# WIFIModule.net
KiCad netlist of a schematic drawn in Altium Designer
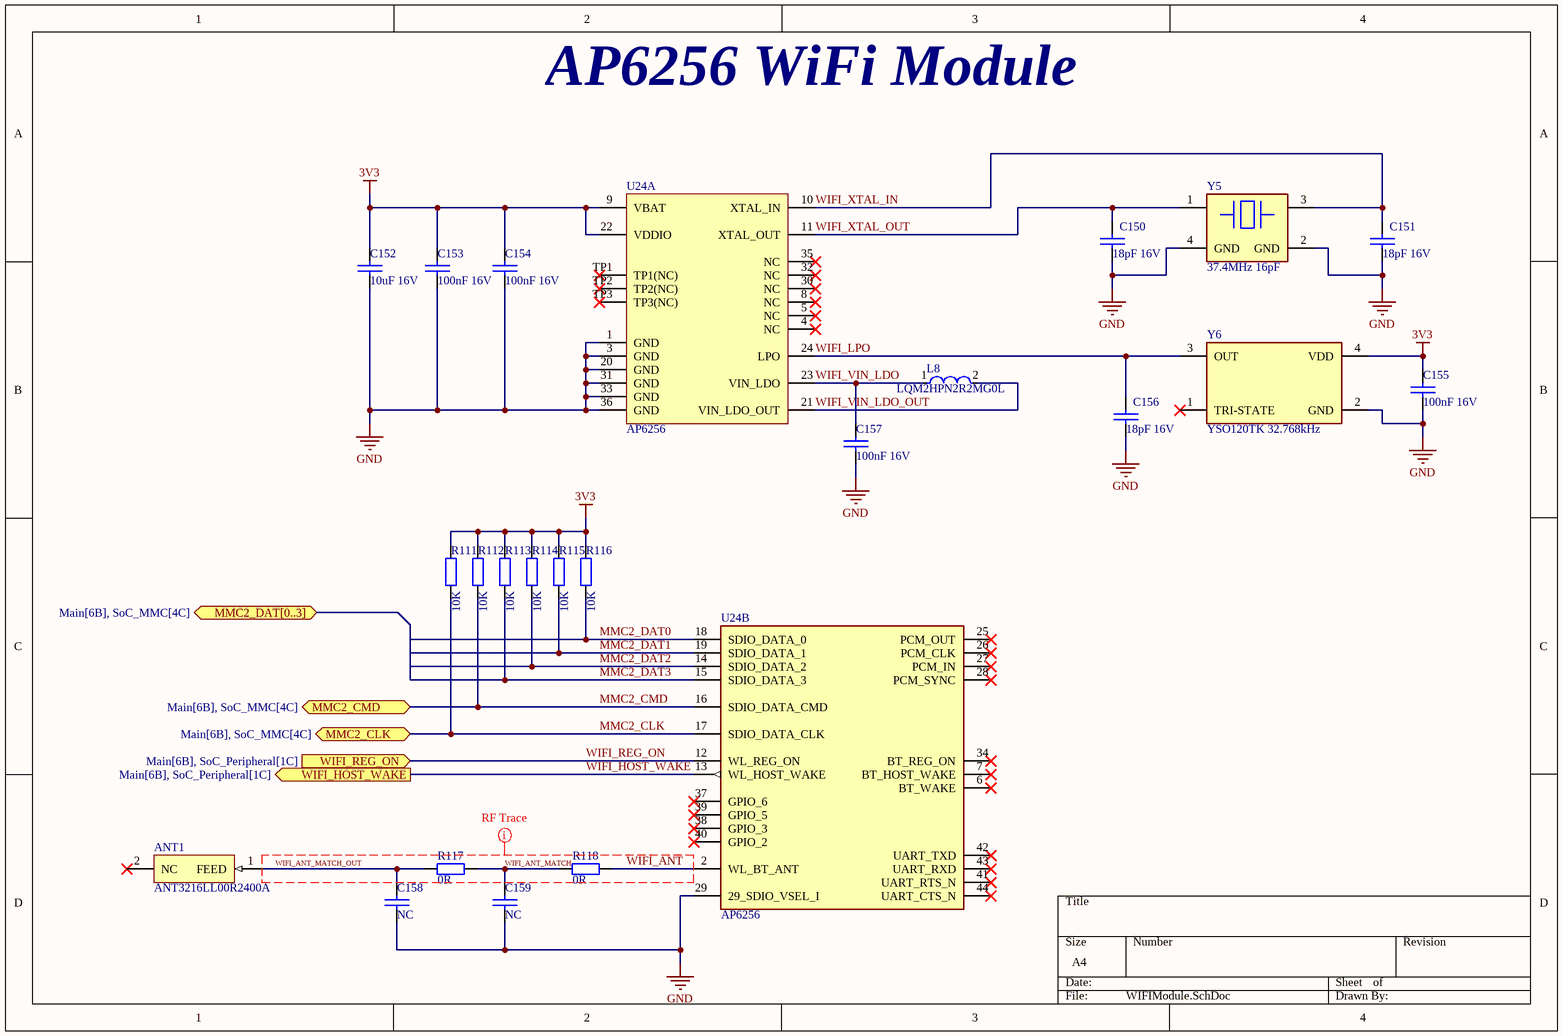
[diagram p0: WIFIModule.SchDoc]

(export (version "E")
  (design (tool "Eeschema 10.0.6"))
  (components
    (comp (ref "ANT1")
      (value "ANT3216LL00R2400A")
      (footprint "ANT_1206")
      (description "5.05dBi Chip Antenna Linear 160MHz 2450MHz 1W 1206 Antennas ROHS")
      (fields (field (name "MANUFACTURER") "YAGEO"))
      (libsource (lib "tor1kkLib") (part "ANT3216LL00R2400A"))
    )
    (comp (ref "C150")
      (value "18pF 16V")
      (footprint "C_0402")
      (description "Capacitor 0402 SMD")
      (libsource (lib "tor1kkLib") (part "C_0402"))
    )
    (comp (ref "C151")
      (value "18pF 16V")
      (footprint "C_0402")
      (description "Capacitor 0402 SMD")
      (libsource (lib "tor1kkLib") (part "C_0402"))
    )
    (comp (ref "C152")
      (value "10uF 16V")
      (footprint "C_0603")
      (description "Capacitor 0603 SMD")
      (libsource (lib "tor1kkLib") (part "C_0603"))
    )
    (comp (ref "C153")
      (value "100nF 16V")
      (footprint "C_0402")
      (description "Capacitor 0402 SMD")
      (libsource (lib "tor1kkLib") (part "C_0402"))
    )
    (comp (ref "C154")
      (value "100nF 16V")
      (footprint "C_0402")
      (description "Capacitor 0402 SMD")
      (libsource (lib "tor1kkLib") (part "C_0402"))
    )
    (comp (ref "C155")
      (value "100nF 16V")
      (footprint "C_0402")
      (description "Capacitor 0402 SMD")
      (libsource (lib "tor1kkLib") (part "C_0402"))
    )
    (comp (ref "C156")
      (value "18pF 16V")
      (footprint "C_0402")
      (description "Capacitor 0402 SMD")
      (libsource (lib "tor1kkLib") (part "C_0402"))
    )
    (comp (ref "C157")
      (value "100nF 16V")
      (footprint "C_0402")
      (description "Capacitor 0402 SMD")
      (libsource (lib "tor1kkLib") (part "C_0402"))
    )
    (comp (ref "C158")
      (value "NC")
      (footprint "C_0402")
      (description "Capacitor 0402 SMD")
      (libsource (lib "tor1kkLib") (part "C_0402"))
    )
    (comp (ref "C159")
      (value "NC")
      (footprint "C_0402")
      (description "Capacitor 0402 SMD")
      (libsource (lib "tor1kkLib") (part "C_0402"))
    )
    (comp (ref "L8")
      (value "LQM2HPN2R2MG0L")
      (footprint "FP-LQM2HPN_G0-IPC_C")
      (description "Multilayer Type Inductor for Power Lines, 1008 (2520), 2.2μH, 20%, 0.1Ω, 1.3A")
      (fields (field (name "TOLERANCE") "20%"))
      (libsource (lib "Altium Content Vault") (part "725321dda6339637d4d059423bc1c3c"))
    )
    (comp (ref "R111")
      (value "10K")
      (footprint "R_0402")
      (description "Resistor 0402 SMD")
      (libsource (lib "tor1kkLib") (part "R_0402"))
    )
    (comp (ref "R112")
      (value "10K")
      (footprint "R_0402")
      (description "Resistor 0402 SMD")
      (libsource (lib "tor1kkLib") (part "R_0402"))
    )
    (comp (ref "R113")
      (value "10K")
      (footprint "R_0402")
      (description "Resistor 0402 SMD")
      (libsource (lib "tor1kkLib") (part "R_0402"))
    )
    (comp (ref "R114")
      (value "10K")
      (footprint "R_0402")
      (description "Resistor 0402 SMD")
      (libsource (lib "tor1kkLib") (part "R_0402"))
    )
    (comp (ref "R115")
      (value "10K")
      (footprint "R_0402")
      (description "Resistor 0402 SMD")
      (libsource (lib "tor1kkLib") (part "R_0402"))
    )
    (comp (ref "R116")
      (value "10K")
      (footprint "R_0402")
      (description "Resistor 0402 SMD")
      (libsource (lib "tor1kkLib") (part "R_0402"))
    )
    (comp (ref "R117")
      (value "0R")
      (footprint "R_0402")
      (description "Resistor 0402 SMD")
      (libsource (lib "") (part "R_0402_1"))
    )
    (comp (ref "R118")
      (value "0R")
      (footprint "R_0402")
      (description "Resistor 0402 SMD")
      (libsource (lib "") (part "R_0402_1"))
    )
    (comp (ref "U24")
      (value "AP6256")
      (footprint "AP6256")
      (description "Wi-Fi and Bluetooth 802.11a/b/g/n/ac")
      (fields (field (name "MANUFACTURER") "AMPAK Tech"))
      (libsource (lib "tor1kkLib") (part "AP6256"))
    )
    (comp (ref "Y5")
      (value "37.4MHz 16pF")
      (footprint "CRYSTAL_SMD3225-4P")
      (description "37.4MHz 16pF ±10ppm ±10ppm SMD3225-4P Crystals ROHS")
      (fields
        (field (name "MANUFACTURER") "Hosonic Elec")
        (field (name "MANUFACTURER PART NUMBER") "E3SB37E0X0004E")
      )
      (libsource (lib "tor1kkLib") (part "E3SB37E0X0004E"))
    )
    (comp (ref "Y6")
      (value "YSO120TK 32.768kHz")
      (footprint "CRYSTAL_SMD3225-4P")
      (description "1.8V~3.3V ±10ppm ±20ppm CMOS 32.768kHz SMD3225-4P Crystal Oscillators ROHS")
      (fields
        (field (name "MANUFACTURER") "YXC Crystal Oscillators")
        (field (name "MANUFACTURER PART NUMBER") "OK2EL89CJI-111YLC-32.768K")
      )
      (libsource (lib "tor1kkLib") (part "YSO120TK"))
    )
  )
  (nets
    (net (code "1") (name "/MMC2_CLK") (class "Default")
      (node (ref "R111") (pin "1") (pintype "passive"))
      (node (ref "U24") (pin "17") (pinfunction "SDIO_DATA_CLK_17") (pintype "passive"))
    )
    (net (code "2") (name "/MMC2_CMD") (class "Default")
      (node (ref "R112") (pin "1") (pintype "passive"))
      (node (ref "U24") (pin "16") (pinfunction "SDIO_DATA_CMD_16") (pintype "passive"))
    )
    (net (code "3") (name "/MMC2_DAT0") (class "Default")
      (node (ref "R116") (pin "1") (pintype "passive"))
      (node (ref "U24") (pin "18") (pinfunction "SDIO_DATA_0_18") (pintype "passive"))
    )
    (net (code "4") (name "/MMC2_DAT1") (class "Default")
      (node (ref "R115") (pin "1") (pintype "passive"))
      (node (ref "U24") (pin "19") (pinfunction "SDIO_DATA_1_19") (pintype "passive"))
    )
    (net (code "5") (name "/MMC2_DAT2") (class "Default")
      (node (ref "R114") (pin "1") (pintype "passive"))
      (node (ref "U24") (pin "14") (pinfunction "SDIO_DATA_2_14") (pintype "passive"))
    )
    (net (code "6") (name "/MMC2_DAT3") (class "Default")
      (node (ref "R113") (pin "1") (pintype "passive"))
      (node (ref "U24") (pin "15") (pinfunction "SDIO_DATA_3_15") (pintype "passive"))
    )
    (net (code "8") (name "/WIFI_ANT") (class "Default")
      (node (ref "R118") (pin "2") (pintype "passive"))
      (node (ref "U24") (pin "2") (pinfunction "WL_BT_ANT_2") (pintype "passive"))
    )
    (net (code "9") (name "/WIFI_ANT_MATCH") (class "Default")
      (node (ref "C159") (pin "1") (pintype "passive"))
      (node (ref "R117") (pin "2") (pintype "passive"))
      (node (ref "R118") (pin "1") (pintype "passive"))
    )
    (net (code "10") (name "/WIFI_ANT_MATCH_OUT") (class "Default")
      (node (ref "ANT1") (pin "1") (pinfunction "FEED_1") (pintype "input"))
      (node (ref "C158") (pin "1") (pintype "passive"))
      (node (ref "R117") (pin "1") (pintype "passive"))
    )
    (net (code "11") (name "/WIFI_HOST_WAKE") (class "Default")
      (node (ref "U24") (pin "13") (pinfunction "WL_HOST_WAKE_13") (pintype "output"))
    )
    (net (code "12") (name "/WIFI_LPO") (class "Default")
      (node (ref "C156") (pin "2") (pintype "passive"))
      (node (ref "U24") (pin "24") (pinfunction "LPO_24") (pintype "passive"))
      (node (ref "Y6") (pin "3") (pinfunction "OUT_3") (pintype "passive"))
    )
    (net (code "13") (name "/WIFI_REG_ON") (class "Default")
      (node (ref "U24") (pin "12") (pinfunction "WL_REG_ON_12") (pintype "passive"))
    )
    (net (code "14") (name "/WIFI_VIN_LDO") (class "Default")
      (node (ref "C157") (pin "1") (pintype "passive"))
      (node (ref "L8") (pin "1") (pinfunction "1_1") (pintype "passive"))
      (node (ref "U24") (pin "23") (pinfunction "VIN_LDO_23") (pintype "passive"))
    )
    (net (code "15") (name "/WIFI_VIN_LDO_OUT") (class "Default")
      (node (ref "L8") (pin "2") (pinfunction "2_2") (pintype "passive"))
      (node (ref "U24") (pin "21") (pinfunction "VIN_LDO_OUT_21") (pintype "passive"))
    )
    (net (code "16") (name "/WIFI_XTAL_IN") (class "Default")
      (node (ref "C151") (pin "2") (pintype "passive"))
      (node (ref "U24") (pin "10") (pinfunction "XTAL_IN_10") (pintype "passive"))
      (node (ref "Y5") (pin "3") (pinfunction "CRYSTAL_2_3") (pintype "passive"))
    )
    (net (code "17") (name "/WIFI_XTAL_OUT") (class "Default")
      (node (ref "C150") (pin "2") (pintype "passive"))
      (node (ref "U24") (pin "11") (pinfunction "XTAL_OUT_11") (pintype "passive"))
      (node (ref "Y5") (pin "1") (pinfunction "CRYSTAL_1_1") (pintype "passive"))
    )
    (net (code "18") (name "3V3") (class "Default")
      (node (ref "C152") (pin "1") (pintype "passive"))
      (node (ref "C153") (pin "1") (pintype "passive"))
      (node (ref "C154") (pin "1") (pintype "passive"))
      (node (ref "C155") (pin "1") (pintype "passive"))
      (node (ref "R111") (pin "2") (pintype "passive"))
      (node (ref "R112") (pin "2") (pintype "passive"))
      (node (ref "R113") (pin "2") (pintype "passive"))
      (node (ref "R114") (pin "2") (pintype "passive"))
      (node (ref "R115") (pin "2") (pintype "passive"))
      (node (ref "R116") (pin "2") (pintype "passive"))
      (node (ref "U24") (pin "22") (pinfunction "VDDIO_22") (pintype "passive"))
      (node (ref "U24") (pin "9") (pinfunction "VBAT_9") (pintype "passive"))
      (node (ref "Y6") (pin "4") (pinfunction "VDD_4") (pintype "passive"))
    )
    (net (code "19") (name "GND") (class "Default")
      (node (ref "C150") (pin "1") (pintype "passive"))
      (node (ref "C151") (pin "1") (pintype "passive"))
      (node (ref "C152") (pin "2") (pintype "passive"))
      (node (ref "C153") (pin "2") (pintype "passive"))
      (node (ref "C154") (pin "2") (pintype "passive"))
      (node (ref "C155") (pin "2") (pintype "passive"))
      (node (ref "C156") (pin "1") (pintype "passive"))
      (node (ref "C157") (pin "2") (pintype "passive"))
      (node (ref "C158") (pin "2") (pintype "passive"))
      (node (ref "C159") (pin "2") (pintype "passive"))
      (node (ref "U24") (pin "1") (pinfunction "GND_1") (pintype "passive"))
      (node (ref "U24") (pin "20") (pinfunction "GND_20") (pintype "passive"))
      (node (ref "U24") (pin "29") (pinfunction "29_SDIO_VSEL_I_29") (pintype "passive"))
      (node (ref "U24") (pin "3") (pinfunction "GND_3") (pintype "passive"))
      (node (ref "U24") (pin "31") (pinfunction "GND_31") (pintype "passive"))
      (node (ref "U24") (pin "33") (pinfunction "GND_33") (pintype "passive"))
      (node (ref "U24") (pin "36") (pinfunction "GND_36") (pintype "passive"))
      (node (ref "Y5") (pin "2") (pinfunction "GND_2") (pintype "passive"))
      (node (ref "Y5") (pin "4") (pinfunction "GND_4") (pintype "passive"))
      (node (ref "Y6") (pin "2") (pinfunction "GND_2") (pintype "passive"))
    )
    (net (code "20") (name "unconnected-(ANT1-NC-Pad2)") (class "Default")
      (node (ref "ANT1") (pin "2") (pinfunction "NC_2") (pintype "passive+no_connect"))
    )
    (net (code "21") (name "unconnected-(U24A-NC-Pad4)") (class "Default")
      (node (ref "U24") (pin "4") (pinfunction "NC_4") (pintype "passive+no_connect"))
    )
    (net (code "22") (name "unconnected-(U24A-NC-Pad5)") (class "Default")
      (node (ref "U24") (pin "5") (pinfunction "NC_5") (pintype "passive+no_connect"))
    )
    (net (code "23") (name "unconnected-(U24A-NC-Pad8)") (class "Default")
      (node (ref "U24") (pin "8") (pinfunction "NC_8") (pintype "passive+no_connect"))
    )
    (net (code "24") (name "unconnected-(U24A-NC-Pad30)") (class "Default")
      (node (ref "U24") (pin "30") (pinfunction "NC_30") (pintype "passive+no_connect"))
    )
    (net (code "25") (name "unconnected-(U24A-NC-Pad32)") (class "Default")
      (node (ref "U24") (pin "32") (pinfunction "NC_32") (pintype "passive+no_connect"))
    )
    (net (code "26") (name "unconnected-(U24A-NC-Pad35)") (class "Default")
      (node (ref "U24") (pin "35") (pinfunction "NC_35") (pintype "passive+no_connect"))
    )
    (net (code "27") (name "unconnected-(U24A-TP1(NC)-PadTP1)") (class "Default")
      (node (ref "U24") (pin "TP1") (pinfunction "TP1(NC)_TP1") (pintype "passive+no_connect"))
    )
    (net (code "28") (name "unconnected-(U24A-TP2(NC)-PadTP2)") (class "Default")
      (node (ref "U24") (pin "TP2") (pinfunction "TP2(NC)_TP2") (pintype "passive+no_connect"))
    )
    (net (code "29") (name "unconnected-(U24A-TP3(NC)-PadTP3)") (class "Default")
      (node (ref "U24") (pin "TP3") (pinfunction "TP3(NC)_TP3") (pintype "passive+no_connect"))
    )
    (net (code "30") (name "unconnected-(U24B-BT_HOST_WAKE-Pad7)") (class "Default")
      (node (ref "U24") (pin "7") (pinfunction "BT_HOST_WAKE_7") (pintype "passive+no_connect"))
    )
    (net (code "31") (name "unconnected-(U24B-BT_REG_ON-Pad34)") (class "Default")
      (node (ref "U24") (pin "34") (pinfunction "BT_REG_ON_34") (pintype "passive+no_connect"))
    )
    (net (code "32") (name "unconnected-(U24B-BT_WAKE-Pad6)") (class "Default")
      (node (ref "U24") (pin "6") (pinfunction "BT_WAKE_6") (pintype "passive+no_connect"))
    )
    (net (code "33") (name "unconnected-(U24B-GPIO_2-Pad40)") (class "Default")
      (node (ref "U24") (pin "40") (pinfunction "GPIO_2_40") (pintype "passive+no_connect"))
    )
    (net (code "34") (name "unconnected-(U24B-GPIO_3-Pad38)") (class "Default")
      (node (ref "U24") (pin "38") (pinfunction "GPIO_3_38") (pintype "passive+no_connect"))
    )
    (net (code "35") (name "unconnected-(U24B-GPIO_5-Pad39)") (class "Default")
      (node (ref "U24") (pin "39") (pinfunction "GPIO_5_39") (pintype "passive+no_connect"))
    )
    (net (code "36") (name "unconnected-(U24B-GPIO_6-Pad37)") (class "Default")
      (node (ref "U24") (pin "37") (pinfunction "GPIO_6_37") (pintype "passive+no_connect"))
    )
    (net (code "37") (name "unconnected-(U24B-PCM_CLK-Pad26)") (class "Default")
      (node (ref "U24") (pin "26") (pinfunction "PCM_CLK_26") (pintype "passive+no_connect"))
    )
    (net (code "38") (name "unconnected-(U24B-PCM_IN-Pad27)") (class "Default")
      (node (ref "U24") (pin "27") (pinfunction "PCM_IN_27") (pintype "passive+no_connect"))
    )
    (net (code "39") (name "unconnected-(U24B-PCM_OUT-Pad25)") (class "Default")
      (node (ref "U24") (pin "25") (pinfunction "PCM_OUT_25") (pintype "passive+no_connect"))
    )
    (net (code "40") (name "unconnected-(U24B-PCM_SYNC-Pad28)") (class "Default")
      (node (ref "U24") (pin "28") (pinfunction "PCM_SYNC_28") (pintype "passive+no_connect"))
    )
    (net (code "41") (name "unconnected-(U24B-UART_CTS_N-Pad44)") (class "Default")
      (node (ref "U24") (pin "44") (pinfunction "UART_CTS_N_44") (pintype "passive+no_connect"))
    )
    (net (code "42") (name "unconnected-(U24B-UART_RTS_N-Pad41)") (class "Default")
      (node (ref "U24") (pin "41") (pinfunction "UART_RTS_N_41") (pintype "passive+no_connect"))
    )
    (net (code "43") (name "unconnected-(U24B-UART_RXD-Pad43)") (class "Default")
      (node (ref "U24") (pin "43") (pinfunction "UART_RXD_43") (pintype "passive+no_connect"))
    )
    (net (code "44") (name "unconnected-(U24B-UART_TXD-Pad42)") (class "Default")
      (node (ref "U24") (pin "42") (pinfunction "UART_TXD_42") (pintype "passive+no_connect"))
    )
    (net (code "45") (name "unconnected-(Y6-TRI-STATE-Pad1)") (class "Default")
      (node (ref "Y6") (pin "1") (pinfunction "TRI-STATE_1") (pintype "passive+no_connect"))
    )
  )
)
